# 04_AD623.net
KiCad netlist of a schematic drawn in Altium Designer
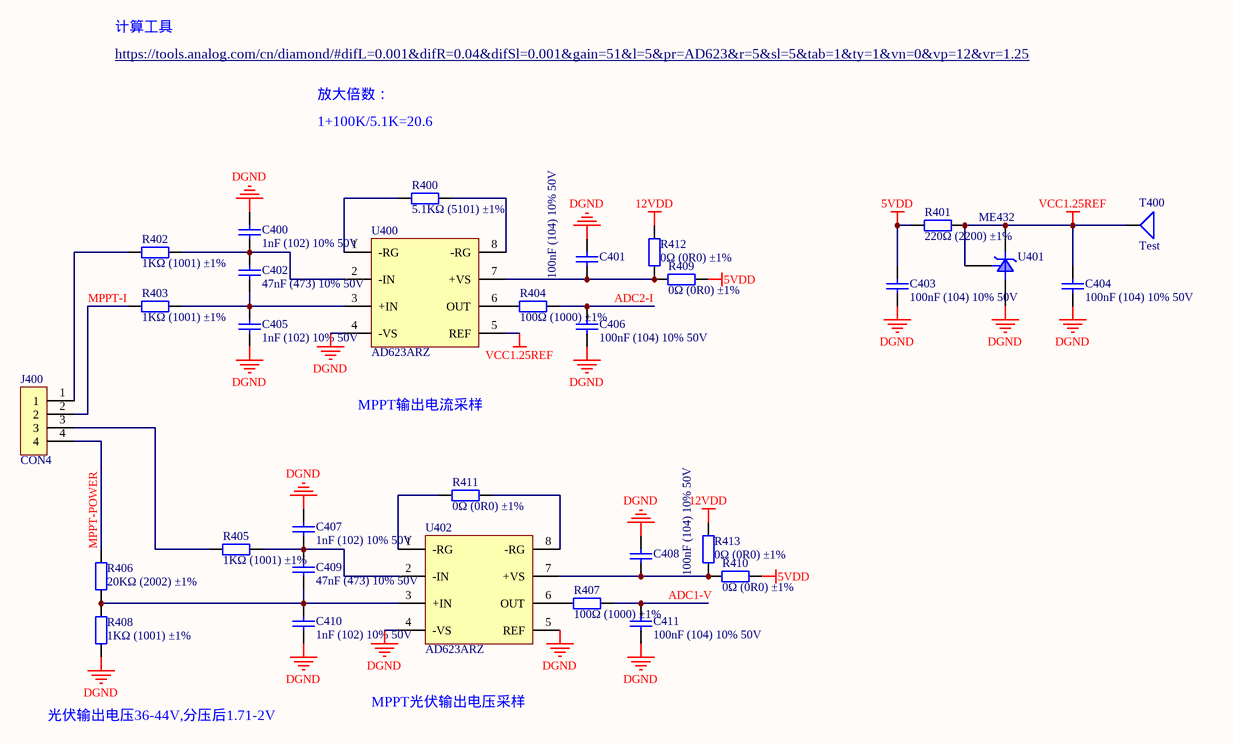
[diagram p0: 04_AD623.SchDoc]

(export (version "E")
  (design (tool "Eeschema 10.0.6"))
  (components
    (comp (ref "C400")
      (value "1nF (102) 10% 50V")
      (footprint "0603_C")
      (description "贴片电容")
      (libsource (lib "Miscellaneous Devices LC") (part "0603 1nF (102) 10% 50V"))
    )
    (comp (ref "C401")
      (value "100nF (104) 10% 50V")
      (footprint "0603_C")
      (description "贴片电容")
      (libsource (lib "Miscellaneous Devices LC") (part "0603 100nF (104) 10% 50V"))
    )
    (comp (ref "C402")
      (value "47nF (473) 10% 50V")
      (footprint "0603_C")
      (description "贴片电容")
      (libsource (lib "Miscellaneous Devices LC") (part "0603 47nF (473) 10% 50V"))
    )
    (comp (ref "C403")
      (value "100nF (104) 10% 50V")
      (footprint "0603_C")
      (description "贴片电容")
      (libsource (lib "Miscellaneous Devices LC") (part "0603 100nF (104) 10% 50V"))
    )
    (comp (ref "C404")
      (value "100nF (104) 10% 50V")
      (footprint "0603_C")
      (description "贴片电容")
      (libsource (lib "Miscellaneous Devices LC") (part "0603 100nF (104) 10% 50V"))
    )
    (comp (ref "C405")
      (value "1nF (102) 10% 50V")
      (footprint "0603_C")
      (description "贴片电容")
      (libsource (lib "Miscellaneous Devices LC") (part "0603 1nF (102) 10% 50V"))
    )
    (comp (ref "C406")
      (value "100nF (104) 10% 50V")
      (footprint "0603_C")
      (description "贴片电容")
      (libsource (lib "Miscellaneous Devices LC") (part "0603 100nF (104) 10% 50V"))
    )
    (comp (ref "C407")
      (value "1nF (102) 10% 50V")
      (footprint "0603_C")
      (description "贴片电容")
      (libsource (lib "Miscellaneous Devices LC") (part "0603 1nF (102) 10% 50V"))
    )
    (comp (ref "C408")
      (value "100nF (104) 10% 50V")
      (footprint "0603_C")
      (description "贴片电容")
      (libsource (lib "Miscellaneous Devices LC") (part "0603 100nF (104) 10% 50V"))
    )
    (comp (ref "C409")
      (value "47nF (473) 10% 50V")
      (footprint "0603_C")
      (description "贴片电容")
      (libsource (lib "Miscellaneous Devices LC") (part "0603 47nF (473) 10% 50V"))
    )
    (comp (ref "C410")
      (value "1nF (102) 10% 50V")
      (footprint "0603_C")
      (description "贴片电容")
      (libsource (lib "Miscellaneous Devices LC") (part "0603 1nF (102) 10% 50V"))
    )
    (comp (ref "C411")
      (value "100nF (104) 10% 50V")
      (footprint "0603_C")
      (description "贴片电容")
      (libsource (lib "Miscellaneous Devices LC") (part "0603 100nF (104) 10% 50V"))
    )
    (comp (ref "J400")
      (value "CON4")
      (footprint "XH2.54-4P")
      (libsource (lib "RayPCB20210502") (part "CON4"))
    )
    (comp (ref "R400")
      (value "5.1KΩ (5101) ±1%")
      (footprint "0603_R")
      (description "贴片电阻")
      (libsource (lib "Miscellaneous Devices LC") (part "0603 5.1KΩ (5101) 1%"))
    )
    (comp (ref "R401")
      (value "220Ω (2200) ±1%")
      (footprint "0603_R")
      (description "贴片电阻")
      (libsource (lib "Miscellaneous Devices LC") (part "0603 220Ω (2200) 1%"))
    )
    (comp (ref "R402")
      (value "1KΩ (1001) ±1%")
      (footprint "0603_R")
      (description "贴片电阻")
      (libsource (lib "") (part "0603 1KΩ (1001) 1%_1"))
    )
    (comp (ref "R403")
      (value "1KΩ (1001) ±1%")
      (footprint "0603_R")
      (description "贴片电阻")
      (libsource (lib "") (part "0603 1KΩ (1001) 1%_1"))
    )
    (comp (ref "R404")
      (value "100Ω (1000) ±1%")
      (footprint "0603_R")
      (description "贴片电阻")
      (libsource (lib "Miscellaneous Devices LC") (part "0603 100Ω (1000) 1%"))
    )
    (comp (ref "R405")
      (value "1KΩ (1001) ±1%")
      (footprint "0603_R")
      (description "贴片电阻")
      (libsource (lib "") (part "0603 1KΩ (1001) 1%_1"))
    )
    (comp (ref "R406")
      (value "20KΩ (2002) ±1%")
      (footprint "0603_R")
      (description "贴片电阻")
      (libsource (lib "Miscellaneous Devices LC") (part "0603 20KΩ (2002) 1%"))
    )
    (comp (ref "R407")
      (value "100Ω (1000) ±1%")
      (footprint "0603_R")
      (description "贴片电阻")
      (libsource (lib "Miscellaneous Devices LC") (part "0603 100Ω (1000) 1%"))
    )
    (comp (ref "R408")
      (value "1KΩ (1001) ±1%")
      (footprint "0603_R")
      (description "贴片电阻")
      (libsource (lib "Miscellaneous Devices LC") (part "0603 1KΩ (1001) 1%"))
    )
    (comp (ref "R409")
      (value "0Ω (0R0) ±1%")
      (footprint "0603_R")
      (description "贴片电阻")
      (libsource (lib "") (part "0603 0Ω (0R0) 1%_1"))
    )
    (comp (ref "R410")
      (value "0Ω (0R0) ±1%")
      (footprint "0603_R")
      (description "贴片电阻")
      (libsource (lib "") (part "0603 0Ω (0R0) 1%_1"))
    )
    (comp (ref "R411")
      (value "0Ω (0R0) ±1%")
      (footprint "0603_R")
      (description "贴片电阻")
      (libsource (lib "") (part "0603 0Ω (0R0) 1%_1"))
    )
    (comp (ref "R412")
      (value "0Ω (0R0) ±1%")
      (footprint "0603_R")
      (description "贴片电阻")
      (libsource (lib "Miscellaneous Devices LC") (part "0603 0Ω (0R0) 1%"))
    )
    (comp (ref "R413")
      (value "0Ω (0R0) ±1%")
      (footprint "0603_R")
      (description "贴片电阻")
      (libsource (lib "Miscellaneous Devices LC") (part "0603 0Ω (0R0) 1%"))
    )
    (comp (ref "T400")
      (value "Test")
      (footprint "Testpoint")
      (libsource (lib "RayPCB20210502") (part "TestPad"))
    )
    (comp (ref "U400")
      (value "AD623ARZ")
      (footprint "SOIC8")
      (libsource (lib "RayPCB20210502") (part "AD623"))
    )
    (comp (ref "U401")
      (value "ME432")
      (footprint "ME432")
      (description "电压基准")
      (libsource (lib "Miscellaneous Devices LC") (part "CJ431 0.5%431"))
    )
    (comp (ref "U402")
      (value "AD623ARZ")
      (footprint "SOIC8")
      (libsource (lib "RayPCB20210502") (part "AD623"))
    )
  )
  (nets
    (net (code "1") (name "/ADC1-V") (class "Default")
      (node (ref "C411") (pin "2") (pinfunction "2_2") (pintype "passive"))
      (node (ref "R407") (pin "2") (pinfunction "2_2") (pintype "passive"))
    )
    (net (code "2") (name "/ADC2-I") (class "Default")
      (node (ref "C406") (pin "2") (pinfunction "2_2") (pintype "passive"))
      (node (ref "R404") (pin "2") (pinfunction "2_2") (pintype "passive"))
    )
    (net (code "3") (name "/MPPT-I") (class "Default")
      (node (ref "J400") (pin "2") (pinfunction "2_2") (pintype "passive"))
      (node (ref "R403") (pin "1") (pinfunction "1_1") (pintype "passive"))
    )
    (net (code "4") (name "/MPPT-POWER") (class "Default")
      (node (ref "J400") (pin "4") (pinfunction "4_4") (pintype "passive"))
      (node (ref "R406") (pin "2") (pinfunction "2_2") (pintype "passive"))
    )
    (net (code "5") (name "5VDD") (class "Default")
      (node (ref "C403") (pin "2") (pinfunction "2_2") (pintype "passive"))
      (node (ref "R401") (pin "1") (pinfunction "1_1") (pintype "passive"))
      (node (ref "R409") (pin "2") (pinfunction "2_2") (pintype "passive"))
      (node (ref "R410") (pin "2") (pinfunction "2_2") (pintype "passive"))
    )
    (net (code "6") (name "12VDD") (class "Default")
      (node (ref "R412") (pin "2") (pinfunction "2_2") (pintype "passive"))
      (node (ref "R413") (pin "2") (pinfunction "2_2") (pintype "passive"))
    )
    (net (code "7") (name "DGND") (class "Default")
      (node (ref "C400") (pin "2") (pinfunction "2_2") (pintype "passive"))
      (node (ref "C401") (pin "2") (pinfunction "2_2") (pintype "passive"))
      (node (ref "C403") (pin "1") (pinfunction "1_1") (pintype "passive"))
      (node (ref "C404") (pin "1") (pinfunction "1_1") (pintype "passive"))
      (node (ref "C405") (pin "1") (pinfunction "1_1") (pintype "passive"))
      (node (ref "C406") (pin "1") (pinfunction "1_1") (pintype "passive"))
      (node (ref "C407") (pin "2") (pinfunction "2_2") (pintype "passive"))
      (node (ref "C408") (pin "2") (pinfunction "2_2") (pintype "passive"))
      (node (ref "C410") (pin "1") (pinfunction "1_1") (pintype "passive"))
      (node (ref "C411") (pin "1") (pinfunction "1_1") (pintype "passive"))
      (node (ref "R408") (pin "1") (pinfunction "1_1") (pintype "passive"))
      (node (ref "U400") (pin "4") (pinfunction "-VS_4") (pintype "passive"))
      (node (ref "U401") (pin "2") (pinfunction "A_2") (pintype "passive"))
      (node (ref "U402") (pin "4") (pinfunction "-VS_4") (pintype "passive"))
      (node (ref "U402") (pin "5") (pinfunction "REF_5") (pintype "passive"))
    )
    (net (code "8") (name "Net-(J400-Pad1)") (class "Default")
      (node (ref "J400") (pin "1") (pinfunction "1_1") (pintype "passive"))
      (node (ref "R402") (pin "1") (pinfunction "1_1") (pintype "passive"))
    )
    (net (code "9") (name "Net-(J400-Pad3)") (class "Default")
      (node (ref "J400") (pin "3") (pinfunction "3_3") (pintype "passive"))
      (node (ref "R405") (pin "1") (pinfunction "1_1") (pintype "passive"))
    )
    (net (code "10") (name "Net-(R400-Pad1)") (class "Default")
      (node (ref "R400") (pin "1") (pinfunction "1_1") (pintype "passive"))
      (node (ref "U400") (pin "1") (pinfunction "-RG_1") (pintype "passive"))
    )
    (net (code "11") (name "Net-(R400-Pad2)") (class "Default")
      (node (ref "R400") (pin "2") (pinfunction "2_2") (pintype "passive"))
      (node (ref "U400") (pin "8") (pinfunction "-RG_8") (pintype "passive"))
    )
    (net (code "12") (name "Net-(R411-Pad1)") (class "Default")
      (node (ref "R411") (pin "1") (pinfunction "1_1") (pintype "passive"))
      (node (ref "U402") (pin "1") (pinfunction "-RG_1") (pintype "passive"))
    )
    (net (code "13") (name "Net-(R411-Pad2)") (class "Default")
      (node (ref "R411") (pin "2") (pinfunction "2_2") (pintype "passive"))
      (node (ref "U402") (pin "8") (pinfunction "-RG_8") (pintype "passive"))
    )
    (net (code "14") (name "Net-(U400-+IN)") (class "Default")
      (node (ref "C402") (pin "1") (pinfunction "1_1") (pintype "passive"))
      (node (ref "C405") (pin "2") (pinfunction "2_2") (pintype "passive"))
      (node (ref "R403") (pin "2") (pinfunction "2_2") (pintype "passive"))
      (node (ref "U400") (pin "3") (pinfunction "+IN_3") (pintype "passive"))
    )
    (net (code "15") (name "Net-(U400-+VS)") (class "Default")
      (node (ref "C401") (pin "1") (pinfunction "1_1") (pintype "passive"))
      (node (ref "R409") (pin "1") (pinfunction "1_1") (pintype "passive"))
      (node (ref "R412") (pin "1") (pinfunction "1_1") (pintype "passive"))
      (node (ref "U400") (pin "7") (pinfunction "+VS_7") (pintype "passive"))
    )
    (net (code "16") (name "Net-(U400--IN)") (class "Default")
      (node (ref "C400") (pin "1") (pinfunction "1_1") (pintype "passive"))
      (node (ref "C402") (pin "2") (pinfunction "2_2") (pintype "passive"))
      (node (ref "R402") (pin "2") (pinfunction "2_2") (pintype "passive"))
      (node (ref "U400") (pin "2") (pinfunction "-IN_2") (pintype "passive"))
    )
    (net (code "17") (name "Net-(U400-OUT)") (class "Default")
      (node (ref "R404") (pin "1") (pinfunction "1_1") (pintype "passive"))
      (node (ref "U400") (pin "6") (pinfunction "OUT_6") (pintype "passive"))
    )
    (net (code "18") (name "Net-(U402-+IN)") (class "Default")
      (node (ref "C409") (pin "1") (pinfunction "1_1") (pintype "passive"))
      (node (ref "C410") (pin "2") (pinfunction "2_2") (pintype "passive"))
      (node (ref "R406") (pin "1") (pinfunction "1_1") (pintype "passive"))
      (node (ref "R408") (pin "2") (pinfunction "2_2") (pintype "passive"))
      (node (ref "U402") (pin "3") (pinfunction "+IN_3") (pintype "passive"))
    )
    (net (code "19") (name "Net-(U402-+VS)") (class "Default")
      (node (ref "C408") (pin "1") (pinfunction "1_1") (pintype "passive"))
      (node (ref "R410") (pin "1") (pinfunction "1_1") (pintype "passive"))
      (node (ref "R413") (pin "1") (pinfunction "1_1") (pintype "passive"))
      (node (ref "U402") (pin "7") (pinfunction "+VS_7") (pintype "passive"))
    )
    (net (code "20") (name "Net-(U402--IN)") (class "Default")
      (node (ref "C407") (pin "1") (pinfunction "1_1") (pintype "passive"))
      (node (ref "C409") (pin "2") (pinfunction "2_2") (pintype "passive"))
      (node (ref "R405") (pin "2") (pinfunction "2_2") (pintype "passive"))
      (node (ref "U402") (pin "2") (pinfunction "-IN_2") (pintype "passive"))
    )
    (net (code "21") (name "Net-(U402-OUT)") (class "Default")
      (node (ref "R407") (pin "1") (pinfunction "1_1") (pintype "passive"))
      (node (ref "U402") (pin "6") (pinfunction "OUT_6") (pintype "passive"))
    )
    (net (code "22") (name "VCC1.25REF") (class "Default")
      (node (ref "C404") (pin "2") (pinfunction "2_2") (pintype "passive"))
      (node (ref "R401") (pin "2") (pinfunction "2_2") (pintype "passive"))
      (node (ref "T400") (pin "1") (pinfunction "1_1") (pintype "passive"))
      (node (ref "U400") (pin "5") (pinfunction "REF_5") (pintype "passive"))
      (node (ref "U401") (pin "1") (pinfunction "R_1") (pintype "passive"))
      (node (ref "U401") (pin "3") (pinfunction "K_3") (pintype "passive"))
    )
  )
)
